# zamekKodowy.net
KiCad netlist of a schematic drawn in EAGLE
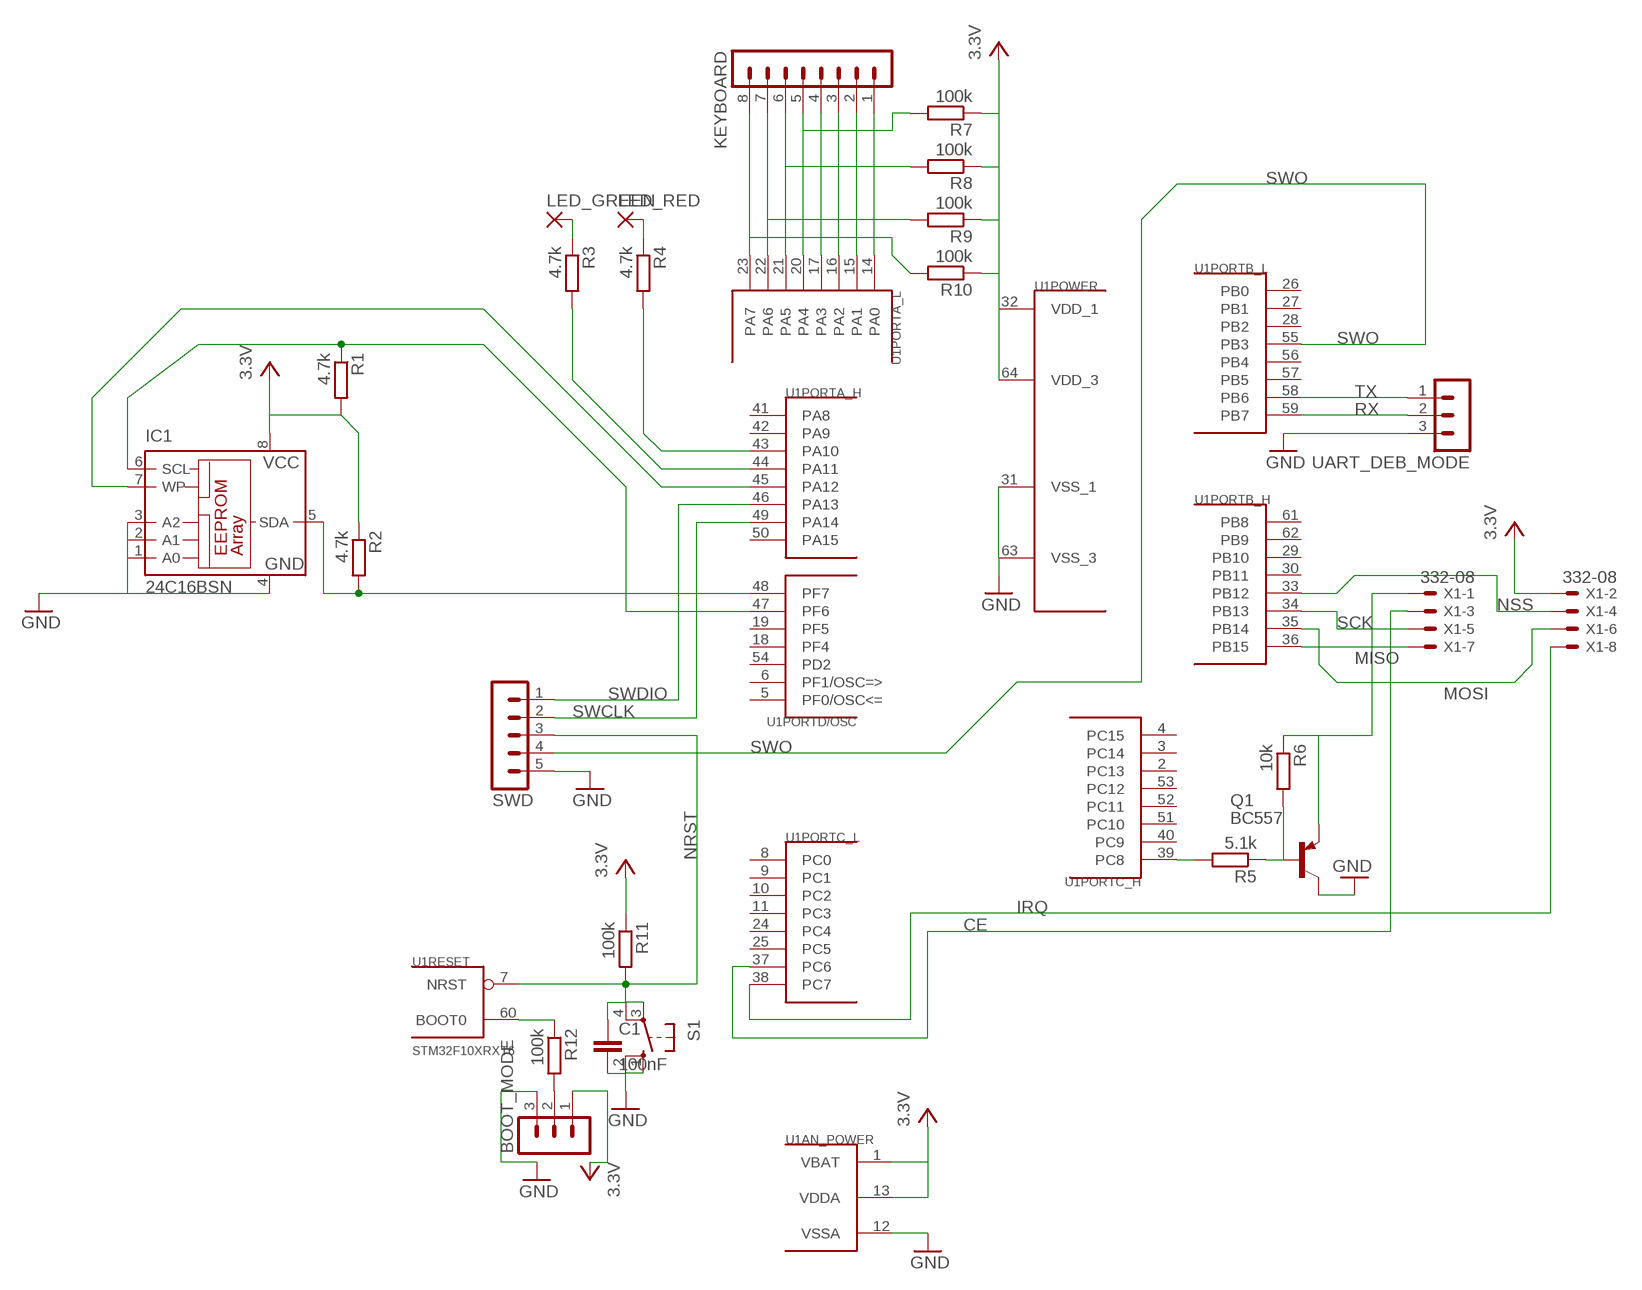
[diagram p0: schematic, sheet 1]

(export (version "E")
  (design (tool "Eeschema 10.0.6"))
  (components
    (comp (ref "BOOT_MODE")
      (value "MA03-1")
      (footprint "eagle-import:MA03-1")
      (fields (field (name "OC_FARNELL") "unknown") (field (name "OC_NEWARK") "unknown"))
      (libsource (lib "eagle-import") (part "MA03-1"))
    )
    (comp (ref "C1")
      (value "100nF")
      (footprint "eagle-import:C1206K")
      (libsource (lib "eagle-import") (part "C-EUC1206K"))
    )
    (comp (ref "IC1")
      (value "24C16BSN")
      (footprint "eagle-import:SO-08")
      (fields (field (name "MPN") "AT24C16BN-SH-B"))
      (libsource (lib "eagle-import") (part "24SNC16B"))
    )
    (comp (ref "KEYBOARD")
      (value "MA08-1")
      (footprint "eagle-import:MA08-1")
      (libsource (lib "eagle-import") (part "MA08-1"))
    )
    (comp (ref "LED_GREEN")
      (value "2,54/0,9")
      (footprint "eagle-import:2,54_0,9")
      (libsource (lib "eagle-import") (part "2,54/0,9"))
    )
    (comp (ref "LED_RED")
      (value "2,54/0,9")
      (footprint "eagle-import:2,54_0,9")
      (libsource (lib "eagle-import") (part "2,54/0,9"))
    )
    (comp (ref "Q1")
      (value "BC557")
      (footprint "eagle-import:TO92")
      (libsource (lib "eagle-import") (part "BC557"))
    )
    (comp (ref "R1")
      (value "4.7k")
      (footprint "eagle-import:M2309")
      (libsource (lib "eagle-import") (part "R-EU_M2309"))
    )
    (comp (ref "R2")
      (value "4.7k")
      (footprint "eagle-import:M2309")
      (libsource (lib "eagle-import") (part "R-EU_M2309"))
    )
    (comp (ref "R3")
      (value "4.7k")
      (footprint "eagle-import:M2309")
      (libsource (lib "eagle-import") (part "R-EU_M2309"))
    )
    (comp (ref "R4")
      (value "4.7k")
      (footprint "eagle-import:M2309")
      (libsource (lib "eagle-import") (part "R-EU_M2309"))
    )
    (comp (ref "R5")
      (value "5.1k")
      (footprint "eagle-import:M2309")
      (libsource (lib "eagle-import") (part "R-EU_M2309"))
    )
    (comp (ref "R6")
      (value "10k")
      (footprint "eagle-import:M2309")
      (libsource (lib "eagle-import") (part "R-EU_M2309"))
    )
    (comp (ref "R7")
      (value "100k")
      (footprint "eagle-import:M2309")
      (libsource (lib "eagle-import") (part "R-EU_M2309"))
    )
    (comp (ref "R8")
      (value "100k")
      (footprint "eagle-import:M2309")
      (libsource (lib "eagle-import") (part "R-EU_M2309"))
    )
    (comp (ref "R9")
      (value "100k")
      (footprint "eagle-import:M2309")
      (libsource (lib "eagle-import") (part "R-EU_M2309"))
    )
    (comp (ref "R10")
      (value "100k")
      (footprint "eagle-import:M2309")
      (libsource (lib "eagle-import") (part "R-EU_M2309"))
    )
    (comp (ref "R11")
      (value "100k")
      (footprint "eagle-import:M2309")
      (libsource (lib "eagle-import") (part "R-EU_M2309"))
    )
    (comp (ref "R12")
      (value "100k")
      (footprint "eagle-import:M2309")
      (libsource (lib "eagle-import") (part "R-EU_M2309"))
    )
    (comp (ref "S1")
      (value "10-XX")
      (footprint "eagle-import:B3F-10XX")
      (fields (field (name "MPN") "B3F-1000"))
      (libsource (lib "eagle-import") (part "10-XX"))
    )
    (comp (ref "SWD")
      (value "MA05-1")
      (footprint "eagle-import:MA05-1")
      (libsource (lib "eagle-import") (part "MA05-1"))
    )
    (comp (ref "U1")
      (value "STM32F10XRXT6")
      (footprint "eagle-import:TQFP64")
      (libsource (lib "eagle-import") (part "STM32F10XRXT6"))
    )
    (comp (ref "UART_DEB_MODE")
      (value "MA03-1")
      (footprint "eagle-import:MA03-1")
      (libsource (lib "eagle-import") (part "MA03-1"))
    )
    (comp (ref "X1")
      (value "332-08")
      (footprint "eagle-import:332-08")
      (libsource (lib "eagle-import") (part "332-08"))
    )
  )
  (nets
    (net (code "1") (name "/CE") (class "Default")
      (node (ref "U1") (pin "37") (pinfunction "PC6_37") (pintype "bidirectional"))
      (node (ref "X1") (pin "3") (pinfunction "S_3") (pintype "passive"))
    )
    (net (code "2") (name "/IRQ") (class "Default")
      (node (ref "U1") (pin "38") (pinfunction "PC7_38") (pintype "bidirectional"))
      (node (ref "X1") (pin "8") (pinfunction "S_8") (pintype "passive"))
    )
    (net (code "3") (name "/MISO") (class "Default")
      (node (ref "U1") (pin "36") (pinfunction "PB15_36") (pintype "bidirectional"))
      (node (ref "X1") (pin "7") (pinfunction "S_7") (pintype "passive"))
    )
    (net (code "4") (name "/MOSI") (class "Default")
      (node (ref "U1") (pin "35") (pinfunction "PB14_35") (pintype "bidirectional"))
      (node (ref "X1") (pin "6") (pinfunction "S_6") (pintype "passive"))
    )
    (net (code "5") (name "/NRST") (class "Default")
      (node (ref "C1") (pin "1") (pinfunction "1_1") (pintype "passive"))
      (node (ref "R11") (pin "2") (pinfunction "2_2") (pintype "passive"))
      (node (ref "S1") (pin "3") (pinfunction "P_3") (pintype "passive"))
      (node (ref "S1") (pin "4") (pinfunction "P1_4") (pintype "passive"))
      (node (ref "SWD") (pin "3") (pinfunction "3_3") (pintype "passive"))
      (node (ref "U1") (pin "7") (pinfunction "NRST_7") (pintype "input"))
    )
    (net (code "6") (name "/NSS") (class "Default")
      (node (ref "U1") (pin "33") (pinfunction "PB12_33") (pintype "bidirectional"))
      (node (ref "X1") (pin "4") (pinfunction "S_4") (pintype "passive"))
    )
    (net (code "7") (name "/RX") (class "Default")
      (node (ref "U1") (pin "59") (pinfunction "PB7_59") (pintype "bidirectional"))
      (node (ref "UART_DEB_MODE") (pin "2") (pinfunction "2_2") (pintype "passive"))
    )
    (net (code "8") (name "/SCK") (class "Default")
      (node (ref "U1") (pin "34") (pinfunction "PB13_34") (pintype "bidirectional"))
      (node (ref "X1") (pin "5") (pinfunction "S_5") (pintype "passive"))
    )
    (net (code "9") (name "/SWCLK") (class "Default")
      (node (ref "SWD") (pin "2") (pinfunction "2_2") (pintype "passive"))
      (node (ref "U1") (pin "49") (pinfunction "PA14_49") (pintype "bidirectional"))
    )
    (net (code "10") (name "/SWDIO") (class "Default")
      (node (ref "SWD") (pin "1") (pinfunction "1_1") (pintype "passive"))
      (node (ref "U1") (pin "46") (pinfunction "PA13_46") (pintype "bidirectional"))
    )
    (net (code "11") (name "/SWO") (class "Default")
      (node (ref "SWD") (pin "4") (pinfunction "4_4") (pintype "passive"))
      (node (ref "U1") (pin "55") (pinfunction "PB3_55") (pintype "bidirectional"))
    )
    (net (code "12") (name "/TX") (class "Default")
      (node (ref "U1") (pin "58") (pinfunction "PB6_58") (pintype "bidirectional"))
      (node (ref "UART_DEB_MODE") (pin "1") (pinfunction "1_1") (pintype "passive"))
    )
    (net (code "13") (name "3.3V") (class "Default")
      (node (ref "BOOT_MODE") (pin "1") (pinfunction "1_1") (pintype "passive"))
      (node (ref "IC1") (pin "8") (pinfunction "VCC_8") (pintype "power_in"))
      (node (ref "R1") (pin "2") (pinfunction "2_2") (pintype "passive"))
      (node (ref "R10") (pin "1") (pinfunction "1_1") (pintype "passive"))
      (node (ref "R11") (pin "1") (pinfunction "1_1") (pintype "passive"))
      (node (ref "R2") (pin "1") (pinfunction "1_1") (pintype "passive"))
      (node (ref "R7") (pin "1") (pinfunction "1_1") (pintype "passive"))
      (node (ref "R8") (pin "1") (pinfunction "1_1") (pintype "passive"))
      (node (ref "R9") (pin "1") (pinfunction "1_1") (pintype "passive"))
      (node (ref "U1") (pin "1") (pinfunction "VBAT_1") (pintype "power_in"))
      (node (ref "U1") (pin "13") (pinfunction "VDDA_13") (pintype "power_in"))
      (node (ref "U1") (pin "32") (pinfunction "VDD_1_32") (pintype "power_in"))
      (node (ref "U1") (pin "64") (pinfunction "VDD_3_64") (pintype "power_in"))
      (node (ref "X1") (pin "2") (pinfunction "S_2") (pintype "passive"))
    )
    (net (code "14") (name "GND") (class "Default")
      (node (ref "BOOT_MODE") (pin "3") (pinfunction "3_3") (pintype "passive"))
      (node (ref "C1") (pin "2") (pinfunction "2_2") (pintype "passive"))
      (node (ref "IC1") (pin "1") (pinfunction "A0_1") (pintype "input"))
      (node (ref "IC1") (pin "2") (pinfunction "A1_2") (pintype "input"))
      (node (ref "IC1") (pin "3") (pinfunction "A2_3") (pintype "input"))
      (node (ref "IC1") (pin "4") (pinfunction "GND_4") (pintype "power_in"))
      (node (ref "Q1") (pin "3") (pinfunction "C_3") (pintype "passive"))
      (node (ref "S1") (pin "1") (pinfunction "S_1") (pintype "passive"))
      (node (ref "S1") (pin "2") (pinfunction "S1_2") (pintype "passive"))
      (node (ref "SWD") (pin "5") (pinfunction "5_5") (pintype "passive"))
      (node (ref "U1") (pin "12") (pinfunction "VSSA_12") (pintype "power_in"))
      (node (ref "U1") (pin "31") (pinfunction "VSS_1_31") (pintype "power_in"))
      (node (ref "U1") (pin "63") (pinfunction "VSS_3_63") (pintype "power_in"))
      (node (ref "UART_DEB_MODE") (pin "3") (pinfunction "3_3") (pintype "passive"))
    )
    (net (code "15") (name "Net-(BOOT_MODE-Pad2)") (class "Default")
      (node (ref "BOOT_MODE") (pin "2") (pinfunction "2_2") (pintype "passive"))
      (node (ref "R12") (pin "2") (pinfunction "2_2") (pintype "passive"))
    )
    (net (code "16") (name "Net-(IC1-SCL)") (class "Default")
      (node (ref "IC1") (pin "6") (pinfunction "SCL_6") (pintype "input"))
      (node (ref "R1") (pin "1") (pinfunction "1_1") (pintype "passive"))
      (node (ref "U1") (pin "47") (pinfunction "PF6_47") (pintype "bidirectional"))
    )
    (net (code "17") (name "Net-(IC1-SDA)") (class "Default")
      (node (ref "IC1") (pin "5") (pinfunction "SDA_5") (pintype "bidirectional"))
      (node (ref "R2") (pin "2") (pinfunction "2_2") (pintype "passive"))
      (node (ref "U1") (pin "48") (pinfunction "PF7_48") (pintype "bidirectional"))
    )
    (net (code "18") (name "Net-(IC1-WP)") (class "Default")
      (node (ref "IC1") (pin "7") (pinfunction "WP_7") (pintype "input"))
      (node (ref "U1") (pin "45") (pinfunction "PA12_45") (pintype "bidirectional"))
    )
    (net (code "19") (name "Net-(LED_GREEN-P)") (class "Default")
      (node (ref "LED_GREEN") (pin "1") (pinfunction "P_1") (pintype "passive"))
      (node (ref "R3") (pin "1") (pinfunction "1_1") (pintype "passive"))
    )
    (net (code "20") (name "Net-(LED_RED-P)") (class "Default")
      (node (ref "LED_RED") (pin "1") (pinfunction "P_1") (pintype "passive"))
      (node (ref "R4") (pin "1") (pinfunction "1_1") (pintype "passive"))
    )
    (net (code "21") (name "Net-(Q1-B)") (class "Default")
      (node (ref "Q1") (pin "2") (pinfunction "B_2") (pintype "passive"))
      (node (ref "R5") (pin "1") (pinfunction "1_1") (pintype "passive"))
      (node (ref "R6") (pin "2") (pinfunction "2_2") (pintype "passive"))
    )
    (net (code "22") (name "Net-(Q1-E)") (class "Default")
      (node (ref "Q1") (pin "1") (pinfunction "E_1") (pintype "passive"))
      (node (ref "R6") (pin "1") (pinfunction "1_1") (pintype "passive"))
      (node (ref "X1") (pin "1") (pinfunction "S_1") (pintype "passive"))
    )
    (net (code "23") (name "Net-(U1B-PA10)") (class "Default")
      (node (ref "R4") (pin "2") (pinfunction "2_2") (pintype "passive"))
      (node (ref "U1") (pin "43") (pinfunction "PA10_43") (pintype "bidirectional"))
    )
    (net (code "24") (name "Net-(U1B-PA11)") (class "Default")
      (node (ref "R3") (pin "2") (pinfunction "2_2") (pintype "passive"))
      (node (ref "U1") (pin "44") (pinfunction "PA11_44") (pintype "bidirectional"))
    )
    (net (code "25") (name "Net-(U1C-PA0)") (class "Default")
      (node (ref "KEYBOARD") (pin "1") (pinfunction "1_1") (pintype "passive"))
      (node (ref "U1") (pin "14") (pinfunction "PA0_14") (pintype "bidirectional"))
    )
    (net (code "26") (name "Net-(U1C-PA1)") (class "Default")
      (node (ref "KEYBOARD") (pin "2") (pinfunction "2_2") (pintype "passive"))
      (node (ref "U1") (pin "15") (pinfunction "PA1_15") (pintype "bidirectional"))
    )
    (net (code "27") (name "Net-(U1C-PA2)") (class "Default")
      (node (ref "KEYBOARD") (pin "3") (pinfunction "3_3") (pintype "passive"))
      (node (ref "U1") (pin "16") (pinfunction "PA2_16") (pintype "bidirectional"))
    )
    (net (code "28") (name "Net-(U1C-PA3)") (class "Default")
      (node (ref "KEYBOARD") (pin "4") (pinfunction "4_4") (pintype "passive"))
      (node (ref "U1") (pin "17") (pinfunction "PA3_17") (pintype "bidirectional"))
    )
    (net (code "29") (name "Net-(U1C-PA4)") (class "Default")
      (node (ref "KEYBOARD") (pin "5") (pinfunction "5_5") (pintype "passive"))
      (node (ref "R7") (pin "2") (pinfunction "2_2") (pintype "passive"))
      (node (ref "U1") (pin "20") (pinfunction "PA4_20") (pintype "bidirectional"))
    )
    (net (code "30") (name "Net-(U1C-PA5)") (class "Default")
      (node (ref "KEYBOARD") (pin "6") (pinfunction "6_6") (pintype "passive"))
      (node (ref "R8") (pin "2") (pinfunction "2_2") (pintype "passive"))
      (node (ref "U1") (pin "21") (pinfunction "PA5_21") (pintype "bidirectional"))
    )
    (net (code "31") (name "Net-(U1C-PA6)") (class "Default")
      (node (ref "KEYBOARD") (pin "7") (pinfunction "7_7") (pintype "passive"))
      (node (ref "R9") (pin "2") (pinfunction "2_2") (pintype "passive"))
      (node (ref "U1") (pin "22") (pinfunction "PA6_22") (pintype "bidirectional"))
    )
    (net (code "32") (name "Net-(U1C-PA7)") (class "Default")
      (node (ref "KEYBOARD") (pin "8") (pinfunction "8_8") (pintype "passive"))
      (node (ref "R10") (pin "2") (pinfunction "2_2") (pintype "passive"))
      (node (ref "U1") (pin "23") (pinfunction "PA7_23") (pintype "bidirectional"))
    )
    (net (code "33") (name "Net-(U1F-PC8)") (class "Default")
      (node (ref "R5") (pin "2") (pinfunction "2_2") (pintype "passive"))
      (node (ref "U1") (pin "39") (pinfunction "PC8_39") (pintype "bidirectional"))
    )
    (net (code "34") (name "Net-(U1J-BOOT0)") (class "Default")
      (node (ref "R12") (pin "1") (pinfunction "1_1") (pintype "passive"))
      (node (ref "U1") (pin "60") (pinfunction "BOOT0_60") (pintype "input"))
    )
    (net (code "35") (name "unconnected-(U1B-PA8-Pad41)") (class "Default")
      (node (ref "U1") (pin "41") (pinfunction "PA8_41") (pintype "bidirectional"))
    )
    (net (code "36") (name "unconnected-(U1B-PA9-Pad42)") (class "Default")
      (node (ref "U1") (pin "42") (pinfunction "PA9_42") (pintype "bidirectional"))
    )
    (net (code "37") (name "unconnected-(U1B-PA15-Pad50)") (class "Default")
      (node (ref "U1") (pin "50") (pinfunction "PA15_50") (pintype "bidirectional"))
    )
    (net (code "38") (name "unconnected-(U1D-PB8-Pad61)") (class "Default")
      (node (ref "U1") (pin "61") (pinfunction "PB8_61") (pintype "bidirectional"))
    )
    (net (code "39") (name "unconnected-(U1D-PB9-Pad62)") (class "Default")
      (node (ref "U1") (pin "62") (pinfunction "PB9_62") (pintype "bidirectional"))
    )
    (net (code "40") (name "unconnected-(U1D-PB10-Pad29)") (class "Default")
      (node (ref "U1") (pin "29") (pinfunction "PB10_29") (pintype "bidirectional"))
    )
    (net (code "41") (name "unconnected-(U1D-PB11-Pad30)") (class "Default")
      (node (ref "U1") (pin "30") (pinfunction "PB11_30") (pintype "bidirectional"))
    )
    (net (code "42") (name "unconnected-(U1E-PB0-Pad26)") (class "Default")
      (node (ref "U1") (pin "26") (pinfunction "PB0_26") (pintype "bidirectional"))
    )
    (net (code "43") (name "unconnected-(U1E-PB1-Pad27)") (class "Default")
      (node (ref "U1") (pin "27") (pinfunction "PB1_27") (pintype "bidirectional"))
    )
    (net (code "44") (name "unconnected-(U1E-PB2-Pad28)") (class "Default")
      (node (ref "U1") (pin "28") (pinfunction "PB2_28") (pintype "bidirectional"))
    )
    (net (code "45") (name "unconnected-(U1E-PB4-Pad56)") (class "Default")
      (node (ref "U1") (pin "56") (pinfunction "PB4_56") (pintype "bidirectional"))
    )
    (net (code "46") (name "unconnected-(U1E-PB5-Pad57)") (class "Default")
      (node (ref "U1") (pin "57") (pinfunction "PB5_57") (pintype "bidirectional"))
    )
    (net (code "47") (name "unconnected-(U1F-PC9-Pad40)") (class "Default")
      (node (ref "U1") (pin "40") (pinfunction "PC9_40") (pintype "bidirectional"))
    )
    (net (code "48") (name "unconnected-(U1F-PC10-Pad51)") (class "Default")
      (node (ref "U1") (pin "51") (pinfunction "PC10_51") (pintype "bidirectional"))
    )
    (net (code "49") (name "unconnected-(U1F-PC11-Pad52)") (class "Default")
      (node (ref "U1") (pin "52") (pinfunction "PC11_52") (pintype "bidirectional"))
    )
    (net (code "50") (name "unconnected-(U1F-PC12-Pad53)") (class "Default")
      (node (ref "U1") (pin "53") (pinfunction "PC12_53") (pintype "bidirectional"))
    )
    (net (code "51") (name "unconnected-(U1F-PC13-Pad2)") (class "Default")
      (node (ref "U1") (pin "2") (pinfunction "PC13_2") (pintype "bidirectional"))
    )
    (net (code "52") (name "unconnected-(U1F-PC14-Pad3)") (class "Default")
      (node (ref "U1") (pin "3") (pinfunction "PC14_3") (pintype "bidirectional"))
    )
    (net (code "53") (name "unconnected-(U1F-PC15-Pad4)") (class "Default")
      (node (ref "U1") (pin "4") (pinfunction "PC15_4") (pintype "bidirectional"))
    )
    (net (code "54") (name "unconnected-(U1G-PC0-Pad8)") (class "Default")
      (node (ref "U1") (pin "8") (pinfunction "PC0_8") (pintype "bidirectional"))
    )
    (net (code "55") (name "unconnected-(U1G-PC1-Pad9)") (class "Default")
      (node (ref "U1") (pin "9") (pinfunction "PC1_9") (pintype "bidirectional"))
    )
    (net (code "56") (name "unconnected-(U1G-PC2-Pad10)") (class "Default")
      (node (ref "U1") (pin "10") (pinfunction "PC2_10") (pintype "bidirectional"))
    )
    (net (code "57") (name "unconnected-(U1G-PC3-Pad11)") (class "Default")
      (node (ref "U1") (pin "11") (pinfunction "PC3_11") (pintype "bidirectional"))
    )
    (net (code "58") (name "unconnected-(U1G-PC4-Pad24)") (class "Default")
      (node (ref "U1") (pin "24") (pinfunction "PC4_24") (pintype "bidirectional"))
    )
    (net (code "59") (name "unconnected-(U1G-PC5-Pad25)") (class "Default")
      (node (ref "U1") (pin "25") (pinfunction "PC5_25") (pintype "bidirectional"))
    )
    (net (code "60") (name "unconnected-(U1H-PD2-Pad54)") (class "Default")
      (node (ref "U1") (pin "54") (pinfunction "PD2_54") (pintype "bidirectional"))
    )
    (net (code "61") (name "unconnected-(U1H-PF0{slash}OSC<=-Pad5)") (class "Default")
      (node (ref "U1") (pin "5") (pinfunction "PF0/OSC<=_5") (pintype "bidirectional"))
    )
    (net (code "62") (name "unconnected-(U1H-PF1{slash}OSC=>-Pad6)") (class "Default")
      (node (ref "U1") (pin "6") (pinfunction "PF1/OSC=>_6") (pintype "bidirectional"))
    )
    (net (code "63") (name "unconnected-(U1H-PF4-Pad18)") (class "Default")
      (node (ref "U1") (pin "18") (pinfunction "PF4_18") (pintype "bidirectional"))
    )
    (net (code "64") (name "unconnected-(U1H-PF5-Pad19)") (class "Default")
      (node (ref "U1") (pin "19") (pinfunction "PF5_19") (pintype "bidirectional"))
    )
  )
)
